# DiPho_PoE_adapter.net
KiCad netlist of a schematic drawn in Altium Designer
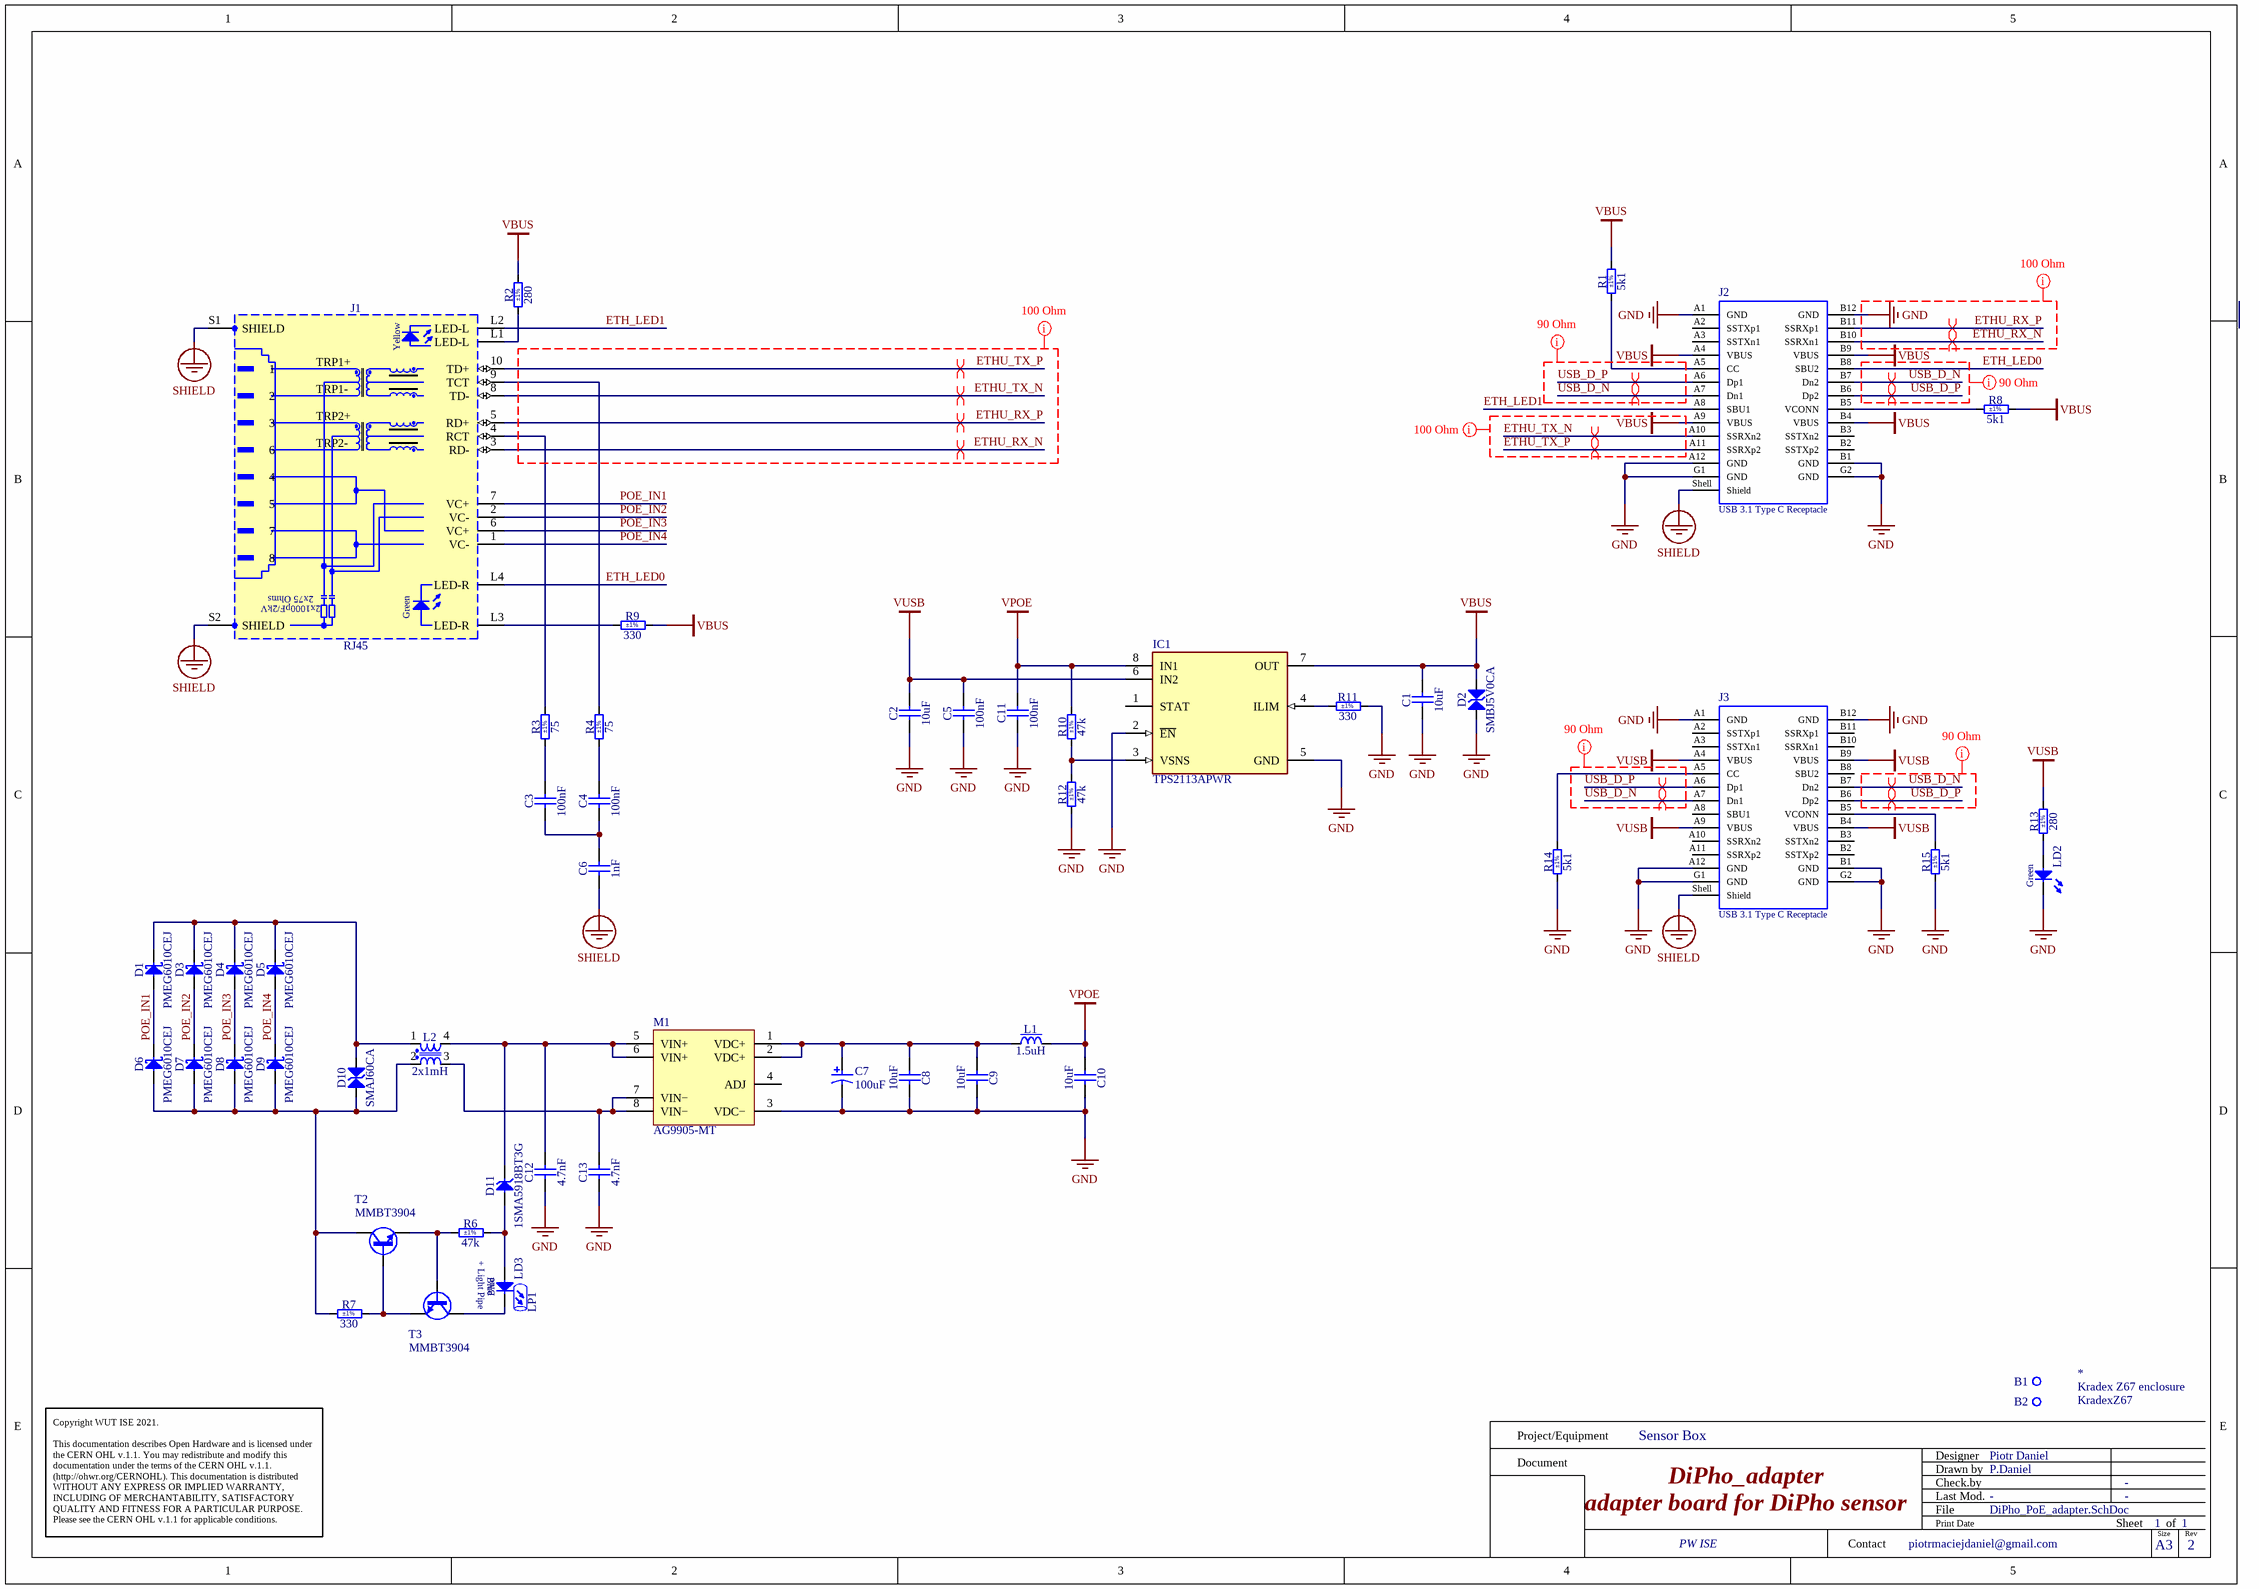
[diagram p0: DiPho_PoE_adapter.SchDoc]

(export (version "E")
  (design (tool "Eeschema 10.0.6"))
  (components
    (comp (ref "*") (value "KradexZ67") (footprint "KradexZ67") (libsource (lib "DiPho") (part "KradexZ67")))
    (comp (ref "B1")
      (value "Plated Hole")
      (footprint "MTG300_600")
      (description "Single Terminal Socket")
      (fields (field (name "PART NUMBER") "PLATED_HOLE3.0_PAD6.0") (field (name "AUTHOR") "CERN DEM JLC"))
      (libsource (lib "Eletro-mechanical") (part "Single Terminal Socket"))
    )
    (comp (ref "B2")
      (value "Plated Hole")
      (footprint "MTG300_600")
      (description "Single Terminal Socket")
      (fields (field (name "PART NUMBER") "PLATED_HOLE3.0_PAD6.0") (field (name "AUTHOR") "CERN DEM JLC"))
      (libsource (lib "Eletro-mechanical") (part "Single Terminal Socket"))
    )
    (comp (ref "C1")
      (value "10uF")
      (footprint "CAPC3225X270N")
      (description "Non-polarised capacitor")
      (fields
        (field (name "PART NUMBER") "CC1210_10UF_25V_10%_X7R")
        (field (name "VOLTAGE") "25V")
        (field (name "AUTHOR") "CERN DEM JLC")
      )
      (libsource (lib "Capacitors") (part "Capacitor - non polarized"))
    )
    (comp (ref "C2")
      (value "10uF")
      (footprint "CAPC3225X270N")
      (description "Non-polarised capacitor")
      (fields
        (field (name "PART NUMBER") "CC1210_10UF_25V_10%_X7R")
        (field (name "VOLTAGE") "25V")
        (field (name "AUTHOR") "CERN DEM JLC")
      )
      (libsource (lib "Capacitors") (part "Capacitor - non polarized"))
    )
    (comp (ref "C3")
      (value "100nF")
      (footprint "CAPC1608X90N")
      (description "Non-polarised capacitor")
      (fields
        (field (name "PART NUMBER") "CC0603_100NF_100V_10%_X7R")
        (field (name "VOLTAGE") "100V")
        (field (name "AUTHOR") "CERN DEM JLC")
      )
      (libsource (lib "Capacitors") (part "Capacitor - non polarized"))
    )
    (comp (ref "C4")
      (value "100nF")
      (footprint "CAPC1608X90N")
      (description "Non-polarised capacitor")
      (fields
        (field (name "PART NUMBER") "CC0603_100NF_100V_10%_X7R")
        (field (name "VOLTAGE") "100V")
        (field (name "AUTHOR") "CERN DEM JLC")
      )
      (libsource (lib "Capacitors") (part "Capacitor - non polarized"))
    )
    (comp (ref "C5")
      (value "100nF")
      (footprint "CAPC1608X90N")
      (description "Non-polarised capacitor")
      (fields
        (field (name "PART NUMBER") "CC0603_100NF_100V_10%_X7R")
        (field (name "VOLTAGE") "100V")
        (field (name "AUTHOR") "CERN DEM JLC")
      )
      (libsource (lib "Capacitors") (part "Capacitor - non polarized"))
    )
    (comp (ref "C6")
      (value "1nF")
      (footprint "CAPC3216X180N")
      (description "Non-polarised capacitor")
      (fields
        (field (name "PART NUMBER") "CC1206_1NF_2KV_10%_X7R")
        (field (name "VOLTAGE") "2kV")
        (field (name "AUTHOR") "CERN DEM JLC")
      )
      (libsource (lib "Capacitors") (part "Capacitor - non polarized"))
    )
    (comp (ref "C7")
      (value "100uF")
      (footprint "PNSC-EEEFK1C101P_L")
      (fields (field (name "MANUFACTURER") "Panasonic"))
      (libsource (lib "Altium Content Vault") (part "CAP-P-2"))
    )
    (comp (ref "C8")
      (value "10uF")
      (footprint "CAPC3225X270N")
      (description "Non-polarised capacitor")
      (fields
        (field (name "PART NUMBER") "CC1210_10UF_25V_10%_X7R")
        (field (name "VOLTAGE") "25V")
        (field (name "AUTHOR") "CERN DEM JLC")
      )
      (libsource (lib "Capacitors") (part "Capacitor - non polarized"))
    )
    (comp (ref "C9")
      (value "10uF")
      (footprint "CAPC3225X270N")
      (description "Non-polarised capacitor")
      (fields
        (field (name "PART NUMBER") "CC1210_10UF_25V_10%_X7R")
        (field (name "VOLTAGE") "25V")
        (field (name "AUTHOR") "CERN DEM JLC")
      )
      (libsource (lib "Capacitors") (part "Capacitor - non polarized"))
    )
    (comp (ref "C10")
      (value "10uF")
      (footprint "CAPC3225X270N")
      (description "Non-polarised capacitor")
      (fields
        (field (name "PART NUMBER") "CC1210_10UF_25V_10%_X7R")
        (field (name "VOLTAGE") "25V")
        (field (name "AUTHOR") "CERN DEM JLC")
      )
      (libsource (lib "Capacitors") (part "Capacitor - non polarized"))
    )
    (comp (ref "C11")
      (value "100nF")
      (footprint "CAPC1608X90N")
      (description "Non-polarised capacitor")
      (fields
        (field (name "PART NUMBER") "CC0603_100NF_100V_10%_X7R")
        (field (name "VOLTAGE") "100V")
        (field (name "AUTHOR") "CERN DEM JLC")
      )
      (libsource (lib "Capacitors") (part "Capacitor - non polarized"))
    )
    (comp (ref "C12")
      (value "4.7nF")
      (footprint "CAPC3216X180N")
      (description "Non-polarised capacitor")
      (fields
        (field (name "PART NUMBER") "CC1206_1NF_2KV_10%_X7R")
        (field (name "VOLTAGE") "2kV")
        (field (name "AUTHOR") "CERN DEM JLC")
      )
      (libsource (lib "Capacitors") (part "Capacitor - non polarized"))
    )
    (comp (ref "C13")
      (value "4.7nF")
      (footprint "CAPC3216X180N")
      (description "Non-polarised capacitor")
      (fields
        (field (name "PART NUMBER") "CC1206_1NF_2KV_10%_X7R")
        (field (name "VOLTAGE") "2kV")
        (field (name "AUTHOR") "CERN DEM JLC")
      )
      (libsource (lib "Capacitors") (part "Capacitor - non polarized"))
    )
    (comp (ref "D1")
      (value "PMEG6010CEJ")
      (footprint "SODFL2513X80N")
      (description "Schottky Diode")
      (fields
        (field (name "VOLTAGE") "60V")
        (field (name "POWER") "1A")
        (field (name "AUTHOR") "CERN DEM BC")
      )
      (libsource (lib "ICs And Semiconductors") (part "Diode Schottky"))
    )
    (comp (ref "D2")
      (value "SMBJ5V0CA")
      (footprint "DIOM5336X265N")
      (description "Transient Voltage Suppressor Diode (Bi-Directional)")
      (fields
        (field (name "VOLTAGE") "5V")
        (field (name "POWER") "600W")
        (field (name "AUTHOR") "CERN DEM JLC")
      )
      (libsource (lib "ICs And Semiconductors") (part "Diode TVS Bi-Directional"))
    )
    (comp (ref "D3")
      (value "PMEG6010CEJ")
      (footprint "SODFL2513X80N")
      (description "Schottky Diode")
      (fields
        (field (name "VOLTAGE") "60V")
        (field (name "POWER") "1A")
        (field (name "AUTHOR") "CERN DEM BC")
      )
      (libsource (lib "ICs And Semiconductors") (part "Diode Schottky"))
    )
    (comp (ref "D4")
      (value "PMEG6010CEJ")
      (footprint "SODFL2513X80N")
      (description "Schottky Diode")
      (fields
        (field (name "VOLTAGE") "60V")
        (field (name "POWER") "1A")
        (field (name "AUTHOR") "CERN DEM BC")
      )
      (libsource (lib "ICs And Semiconductors") (part "Diode Schottky"))
    )
    (comp (ref "D5")
      (value "PMEG6010CEJ")
      (footprint "SODFL2513X80N")
      (description "Schottky Diode")
      (fields
        (field (name "VOLTAGE") "60V")
        (field (name "POWER") "1A")
        (field (name "AUTHOR") "CERN DEM BC")
      )
      (libsource (lib "ICs And Semiconductors") (part "Diode Schottky"))
    )
    (comp (ref "D6")
      (value "PMEG6010CEJ")
      (footprint "SODFL2513X80N")
      (description "Schottky Diode")
      (fields
        (field (name "VOLTAGE") "60V")
        (field (name "POWER") "1A")
        (field (name "AUTHOR") "CERN DEM BC")
      )
      (libsource (lib "ICs And Semiconductors") (part "Diode Schottky"))
    )
    (comp (ref "D7")
      (value "PMEG6010CEJ")
      (footprint "SODFL2513X80N")
      (description "Schottky Diode")
      (fields
        (field (name "VOLTAGE") "60V")
        (field (name "POWER") "1A")
        (field (name "AUTHOR") "CERN DEM BC")
      )
      (libsource (lib "ICs And Semiconductors") (part "Diode Schottky"))
    )
    (comp (ref "D8")
      (value "PMEG6010CEJ")
      (footprint "SODFL2513X80N")
      (description "Schottky Diode")
      (fields
        (field (name "VOLTAGE") "60V")
        (field (name "POWER") "1A")
        (field (name "AUTHOR") "CERN DEM BC")
      )
      (libsource (lib "ICs And Semiconductors") (part "Diode Schottky"))
    )
    (comp (ref "D9")
      (value "PMEG6010CEJ")
      (footprint "SODFL2513X80N")
      (description "Schottky Diode")
      (fields
        (field (name "VOLTAGE") "60V")
        (field (name "POWER") "1A")
        (field (name "AUTHOR") "CERN DEM BC")
      )
      (libsource (lib "ICs And Semiconductors") (part "Diode Schottky"))
    )
    (comp (ref "D10")
      (value "SMAJ60CA")
      (footprint "DIOM5226X262N")
      (description "Transient Voltage Suppressor Diode (Bi-Directional)")
      (fields
        (field (name "VOLTAGE") "60V")
        (field (name "POWER") "400W")
        (field (name "AUTHOR") "CERN DEM JLC")
      )
      (libsource (lib "ICs And Semiconductors") (part "Diode TVS Bi-Directional"))
    )
    (comp (ref "D11")
      (value "1SMA5918BT3G")
      (footprint "DIOM5226X220N")
      (description "Zener Diode")
      (fields
        (field (name "VOLTAGE") "5.1V")
        (field (name "POWER") "1.5W")
        (field (name "AUTHOR") "CERN DEM JLC")
      )
      (libsource (lib "ICs And Semiconductors") (part "Diode Zener"))
    )
    (comp (ref "IC1")
      (value "TPS2113APWR")
      (footprint "FP-PW0008A-MFG")
      (description "IC OR CTRLR SRC SELECT 8TSSOP")
      (libsource (lib "Altium Content Vault") (part "883c2ec5d874d1801bc805f681b0625"))
    )
    (comp (ref "J1")
      (value "RJ45")
      (footprint "ABRACON_ARJM11C7-114-BA-EW2")
      (description "MagJack 10/100BaseT, PoE+, 1X1, OG/Y, -40 to 85*C, Tab Up, RoHS")
      (fields
        (field (name "PART NUMBER") "ARJM11C7-114-BA-EW2")
        (field (name "MANUFACTURER") "Abracon")
        (field (name "AUTHOR") "GK")
      )
      (libsource (lib "DiPho") (part "CON_ETH_POE_ARJM11C7"))
    )
    (comp (ref "J2")
      (value "USB 3.1 Type C Receptacle")
      (footprint "632723300011")
      (description "USB 3.1 Type C, Receptacle, Horizontal, THR")
      (fields
        (field (name "MANUFACTURER") "Wurth Elektronik")
        (field (name "MANUFACTURER PART NUMBER") "632723300011")
      )
      (libsource (lib "WR-USB_USB 3.1") (part "632723300011"))
    )
    (comp (ref "J3")
      (value "USB 3.1 Type C Receptacle")
      (footprint "632723300011")
      (description "USB 3.1 Type C, Receptacle, Horizontal, THR")
      (fields
        (field (name "MANUFACTURER") "Wurth Elektronik")
        (field (name "MANUFACTURER PART NUMBER") "632723300011")
      )
      (libsource (lib "WR-USB_USB 3.1") (part "632723300011"))
    )
    (comp (ref "L1")
      (value "1.5uH")
      (footprint "IND_COILCRAFT_1812CS")
      (description "Inductor With Core")
      (fields
        (field (name "PART NUMBER") "IND_1.5UH_2%_COILCRAFT_1812CS")
        (field (name "POWER") "430mA")
        (field (name "AUTHOR") "CERN DEM JMW")
      )
      (libsource (lib "Inductors & Transformers") (part "Inductor With Magnetic core"))
    )
    (comp (ref "L2")
      (value "2x1mH")
      (footprint "IND_WURTH_WE-SL2")
      (description "Inductor Common Mode")
      (fields
        (field (name "PART NUMBER") "IND_1MH_50%_WURTH_WE-SL2-744222")
        (field (name "POWER") "800mA")
        (field (name "AUTHOR") "CERN DEM JLC")
      )
      (libsource (lib "Inductors & Transformers") (part "Inductor Common Mode 1Dot-4 2Dot-3"))
    )
    (comp (ref "LD2")
      (value "Green")
      (footprint "LED_KINGBRIGHT_KPT-2012ZGC")
      (description "LED Green 1C 2A")
      (fields
        (field (name "PART NUMBER") "LED_KINGBRIGHT_KPT-2012ZGC")
        (field (name "MANUFACTURER") "KINGBRIGHT")
        (field (name "AUTHOR") "CERN DEM BC")
      )
      (libsource (lib "ICs And Semiconductors") (part "LED Green 1C 2A"))
    )
    (comp (ref "LD3")
      (value "Blue")
      (footprint "LED_KINGBRIGHT_KPT-2012VBC-D")
      (description "LED Blue 1C 2A")
      (fields
        (field (name "PART NUMBER") "LED_KINGBRIGHT_KPT-2012VBC-D")
        (field (name "MANUFACTURER") "KINGBRIGHT")
        (field (name "AUTHOR") "CERN DEM BC")
      )
      (libsource (lib "ICs And Semiconductors") (part "LED Blue 1C 2A"))
    )
    (comp (ref "LP1")
      (value "~")
      (footprint "LEDLP_DIALIGHT_515-1049F")
      (description "LED Light Pipe x1 Type1")
      (fields
        (field (name "PART NUMBER") "LEDLP_DIALIGHT_515-1049F")
        (field (name "MANUFACTURER") "DIALIGHT")
        (field (name "AUTHOR") "CERN DEM JLC")
      )
      (libsource (lib "ICs And Semiconductors") (part "LED Light Pipe x1 Type1"))
    )
    (comp (ref "M1")
      (value "AG9905-MT")
      (footprint "SILVERTEL_AG9900")
      (description "Ultra Miniature PoE, 5V, w/Thermal Protection")
      (fields (field (name "MANUFACTURER") "Silvertel"))
      (libsource (lib "DiPho") (part "AG9905-MT"))
    )
    (comp (ref "R1")
      (value "5k1")
      (footprint "RESC1608X55N")
      (description "Resistor - 1%")
      (fields
        (field (name "TOLERANCE") "±1%")
        (field (name "PART NUMBER") "R0603_5K1_1%_0.1W_100PPM")
        (field (name "POWER") "0.1W")
        (field (name "AUTHOR") "CERN DEM JLC")
      )
      (libsource (lib "Resistors") (part "Resistor - 1%"))
    )
    (comp (ref "R2")
      (value "280")
      (footprint "RESC1608X55N")
      (description "Resistor - 1%")
      (fields
        (field (name "TOLERANCE") "±1%")
        (field (name "PART NUMBER") "R0603_280R_1%_0.1W_100PPM")
        (field (name "POWER") "0.1W")
        (field (name "AUTHOR") "CERN DEM JLC")
      )
      (libsource (lib "Resistors") (part "Resistor - 1%"))
    )
    (comp (ref "R3")
      (value "75")
      (footprint "RESC1608X55N")
      (description "Resistor - 1%")
      (fields
        (field (name "TOLERANCE") "±1%")
        (field (name "PART NUMBER") "R0603_75R_1%_0.1W_100PPM")
        (field (name "POWER") "0.1W")
        (field (name "AUTHOR") "CERN DEM JLC")
      )
      (libsource (lib "Resistors") (part "Resistor - 1%"))
    )
    (comp (ref "R4")
      (value "75")
      (footprint "RESC1608X55N")
      (description "Resistor - 1%")
      (fields
        (field (name "TOLERANCE") "±1%")
        (field (name "PART NUMBER") "R0603_75R_1%_0.1W_100PPM")
        (field (name "POWER") "0.1W")
        (field (name "AUTHOR") "CERN DEM JLC")
      )
      (libsource (lib "Resistors") (part "Resistor - 1%"))
    )
    (comp (ref "R6")
      (value "47k")
      (footprint "RESC1608X55N")
      (description "Resistor - 1%")
      (fields
        (field (name "TOLERANCE") "±1%")
        (field (name "PART NUMBER") "R0603_47K_1%_0.1W_100PPM")
        (field (name "POWER") "0.1W")
        (field (name "AUTHOR") "CERN DEM JLC")
      )
      (libsource (lib "Resistors") (part "Resistor - 1%"))
    )
    (comp (ref "R7")
      (value "330")
      (footprint "RESC1608X55N")
      (description "Resistor - 1%")
      (fields
        (field (name "TOLERANCE") "±1%")
        (field (name "PART NUMBER") "R0603_330R_1%_0.1W_100PPM")
        (field (name "POWER") "0.1W")
        (field (name "AUTHOR") "CERN DEM JLC")
      )
      (libsource (lib "Resistors") (part "Resistor - 1%"))
    )
    (comp (ref "R8")
      (value "5k1")
      (footprint "RESC1608X55N")
      (description "Resistor - 1%")
      (fields
        (field (name "TOLERANCE") "±1%")
        (field (name "PART NUMBER") "R0603_5K1_1%_0.1W_100PPM")
        (field (name "POWER") "0.1W")
        (field (name "AUTHOR") "CERN DEM JLC")
      )
      (libsource (lib "Resistors") (part "Resistor - 1%"))
    )
    (comp (ref "R9")
      (value "330")
      (footprint "RESC1608X55N")
      (description "Resistor - 1%")
      (fields
        (field (name "TOLERANCE") "±1%")
        (field (name "PART NUMBER") "R0603_330R_1%_0.1W_100PPM")
        (field (name "POWER") "0.1W")
        (field (name "AUTHOR") "CERN DEM JLC")
      )
      (libsource (lib "Resistors") (part "Resistor - 1%"))
    )
    (comp (ref "R10")
      (value "47k")
      (footprint "RESC1608X55N")
      (description "Resistor - 1%")
      (fields
        (field (name "TOLERANCE") "±1%")
        (field (name "PART NUMBER") "R0603_47K_1%_0.1W_100PPM")
        (field (name "POWER") "0.1W")
        (field (name "AUTHOR") "CERN DEM JLC")
      )
      (libsource (lib "Resistors") (part "Resistor - 1%"))
    )
    (comp (ref "R11")
      (value "330")
      (footprint "RESC1608X55N")
      (description "Resistor - 1%")
      (fields
        (field (name "TOLERANCE") "±1%")
        (field (name "PART NUMBER") "R0603_330R_1%_0.1W_100PPM")
        (field (name "POWER") "0.1W")
        (field (name "AUTHOR") "CERN DEM JLC")
      )
      (libsource (lib "Resistors") (part "Resistor - 1%"))
    )
    (comp (ref "R12")
      (value "47k")
      (footprint "RESC1608X55N")
      (description "Resistor - 1%")
      (fields
        (field (name "TOLERANCE") "±1%")
        (field (name "PART NUMBER") "R0603_47K_1%_0.1W_100PPM")
        (field (name "POWER") "0.1W")
        (field (name "AUTHOR") "CERN DEM JLC")
      )
      (libsource (lib "Resistors") (part "Resistor - 1%"))
    )
    (comp (ref "R13")
      (value "280")
      (footprint "RESC1608X55N")
      (description "Resistor - 1%")
      (fields
        (field (name "TOLERANCE") "±1%")
        (field (name "PART NUMBER") "R0603_280R_1%_0.1W_100PPM")
        (field (name "POWER") "0.1W")
        (field (name "AUTHOR") "CERN DEM JLC")
      )
      (libsource (lib "Resistors") (part "Resistor - 1%"))
    )
    (comp (ref "R14")
      (value "5k1")
      (footprint "RESC1608X55N")
      (description "Resistor - 1%")
      (fields
        (field (name "TOLERANCE") "±1%")
        (field (name "PART NUMBER") "R0603_5K1_1%_0.1W_100PPM")
        (field (name "POWER") "0.1W")
        (field (name "AUTHOR") "CERN DEM JLC")
      )
      (libsource (lib "Resistors") (part "Resistor - 1%"))
    )
    (comp (ref "R15")
      (value "5k1")
      (footprint "RESC1608X55N")
      (description "Resistor - 1%")
      (fields
        (field (name "TOLERANCE") "±1%")
        (field (name "PART NUMBER") "R0603_5K1_1%_0.1W_100PPM")
        (field (name "POWER") "0.1W")
        (field (name "AUTHOR") "CERN DEM JLC")
      )
      (libsource (lib "Resistors") (part "Resistor - 1%"))
    )
    (comp (ref "T2")
      (value "MMBT3904")
      (footprint "SOT95P230X110-3N")
      (description "NPN Transistor")
      (fields (field (name "MANUFACTURER") "NXP SEMICONDUCTORS") (field (name "AUTHOR") "CERN DEM JLC"))
      (libsource (lib "ICs And Semiconductors") (part "NPN B1 E2 C3"))
    )
    (comp (ref "T3")
      (value "MMBT3904")
      (footprint "SOT95P230X110-3N")
      (description "NPN Transistor")
      (fields (field (name "MANUFACTURER") "NXP SEMICONDUCTORS") (field (name "AUTHOR") "CERN DEM JLC"))
      (libsource (lib "ICs And Semiconductors") (part "NPN B1 E2 C3"))
    )
  )
  (nets
    (net (code "1") (name "/ETHU_RX_N") (class "Default")
      (node (ref "J1") (pin "3") (pinfunction "RD-_3") (pintype "bidirectional"))
      (node (ref "J2") (pin "B10") (pinfunction "SSRXn1_B10") (pintype "passive"))
    )
    (net (code "2") (name "/ETHU_RX_P") (class "Default")
      (node (ref "J1") (pin "5") (pinfunction "RD+_5") (pintype "bidirectional"))
      (node (ref "J2") (pin "B11") (pinfunction "SSRXp1_B11") (pintype "passive"))
    )
    (net (code "3") (name "/ETHU_TX_N") (class "Default")
      (node (ref "J1") (pin "8") (pinfunction "TD-_8") (pintype "bidirectional"))
      (node (ref "J2") (pin "A10") (pinfunction "SSRXn2_A10") (pintype "passive"))
    )
    (net (code "4") (name "/ETHU_TX_P") (class "Default")
      (node (ref "J1") (pin "10") (pinfunction "TD+_10") (pintype "bidirectional"))
      (node (ref "J2") (pin "A11") (pinfunction "SSRXp2_A11") (pintype "passive"))
    )
    (net (code "5") (name "/ETH_LED0") (class "Default")
      (node (ref "J1") (pin "L4") (pinfunction "LED-R_L4") (pintype "passive"))
      (node (ref "J2") (pin "B8") (pinfunction "SBU2_B8") (pintype "passive"))
    )
    (net (code "6") (name "/ETH_LED1") (class "Default")
      (node (ref "J1") (pin "L2") (pinfunction "LED-L_L2") (pintype "passive"))
      (node (ref "J2") (pin "A8") (pinfunction "SBU1_A8") (pintype "passive"))
    )
    (net (code "7") (name "/POE_IN1") (class "Default")
      (node (ref "D1") (pin "2") (pinfunction "A_2") (pintype "passive"))
      (node (ref "D6") (pin "1") (pinfunction "C_1") (pintype "passive"))
      (node (ref "J1") (pin "7") (pinfunction "VC+_7") (pintype "passive"))
    )
    (net (code "8") (name "/POE_IN2") (class "Default")
      (node (ref "D3") (pin "2") (pinfunction "A_2") (pintype "passive"))
      (node (ref "D7") (pin "1") (pinfunction "C_1") (pintype "passive"))
      (node (ref "J1") (pin "2") (pinfunction "VC-_2") (pintype "passive"))
    )
    (net (code "9") (name "/POE_IN3") (class "Default")
      (node (ref "D4") (pin "2") (pinfunction "A_2") (pintype "passive"))
      (node (ref "D8") (pin "1") (pinfunction "C_1") (pintype "passive"))
      (node (ref "J1") (pin "6") (pinfunction "VC+_6") (pintype "passive"))
    )
    (net (code "10") (name "/POE_IN4") (class "Default")
      (node (ref "D5") (pin "2") (pinfunction "A_2") (pintype "passive"))
      (node (ref "D9") (pin "1") (pinfunction "C_1") (pintype "passive"))
      (node (ref "J1") (pin "1") (pinfunction "VC-_1") (pintype "passive"))
    )
    (net (code "11") (name "/USB_D_N") (class "Default")
      (node (ref "J2") (pin "A7") (pinfunction "Dn1_A7") (pintype "passive"))
      (node (ref "J2") (pin "B7") (pinfunction "Dn2_B7") (pintype "passive"))
      (node (ref "J3") (pin "A7") (pinfunction "Dn1_A7") (pintype "passive"))
      (node (ref "J3") (pin "B7") (pinfunction "Dn2_B7") (pintype "passive"))
    )
    (net (code "12") (name "/USB_D_P") (class "Default")
      (node (ref "J2") (pin "A6") (pinfunction "Dp1_A6") (pintype "passive"))
      (node (ref "J2") (pin "B6") (pinfunction "Dp2_B6") (pintype "passive"))
      (node (ref "J3") (pin "A6") (pinfunction "Dp1_A6") (pintype "passive"))
      (node (ref "J3") (pin "B6") (pinfunction "Dp2_B6") (pintype "passive"))
    )
    (net (code "13") (name "GND") (class "Default")
      (node (ref "C1") (pin "1") (pinfunction "1_1") (pintype "passive"))
      (node (ref "C10") (pin "2") (pinfunction "2_2") (pintype "passive"))
      (node (ref "C11") (pin "1") (pinfunction "1_1") (pintype "passive"))
      (node (ref "C12") (pin "1") (pinfunction "1_1") (pintype "passive"))
      (node (ref "C13") (pin "1") (pinfunction "1_1") (pintype "passive"))
      (node (ref "C2") (pin "1") (pinfunction "1_1") (pintype "passive"))
      (node (ref "C5") (pin "1") (pinfunction "1_1") (pintype "passive"))
      (node (ref "C7") (pin "2") (pinfunction "2_2") (pintype "passive"))
      (node (ref "C8") (pin "2") (pinfunction "2_2") (pintype "passive"))
      (node (ref "C9") (pin "2") (pinfunction "2_2") (pintype "passive"))
      (node (ref "D2") (pin "1") (pinfunction "1_1") (pintype "passive"))
      (node (ref "IC1") (pin "2") (pinfunction "~{EN}_2") (pintype "input"))
      (node (ref "IC1") (pin "5") (pinfunction "GND_5") (pintype "power_in"))
      (node (ref "J2") (pin "A1") (pinfunction "GND_A1") (pintype "passive"))
      (node (ref "J2") (pin "A12") (pinfunction "GND_A12") (pintype "passive"))
      (node (ref "J2") (pin "B1") (pinfunction "GND_B1") (pintype "passive"))
      (node (ref "J2") (pin "B12") (pinfunction "GND_B12") (pintype "passive"))
      (node (ref "J2") (pin "G1") (pinfunction "GND_G1") (pintype "passive"))
      (node (ref "J2") (pin "G2") (pinfunction "GND_G2") (pintype "passive"))
      (node (ref "J3") (pin "A1") (pinfunction "GND_A1") (pintype "passive"))
      (node (ref "J3") (pin "A12") (pinfunction "GND_A12") (pintype "passive"))
      (node (ref "J3") (pin "B1") (pinfunction "GND_B1") (pintype "passive"))
      (node (ref "J3") (pin "B12") (pinfunction "GND_B12") (pintype "passive"))
      (node (ref "J3") (pin "G1") (pinfunction "GND_G1") (pintype "passive"))
      (node (ref "J3") (pin "G2") (pinfunction "GND_G2") (pintype "passive"))
      (node (ref "LD2") (pin "1") (pinfunction "C_1") (pintype "passive"))
      (node (ref "M1") (pin "3") (pinfunction "VDC−_3") (pintype "passive"))
      (node (ref "R11") (pin "2") (pinfunction "2_2") (pintype "passive"))
      (node (ref "R12") (pin "1") (pinfunction "1_1") (pintype "passive"))
      (node (ref "R14") (pin "1") (pinfunction "1_1") (pintype "passive"))
      (node (ref "R15") (pin "1") (pinfunction "1_1") (pintype "passive"))
    )
    (net (code "14") (name "Net-(C3-Pad1)") (class "Default")
      (node (ref "C3") (pin "1") (pinfunction "1_1") (pintype "passive"))
      (node (ref "C4") (pin "1") (pinfunction "1_1") (pintype "passive"))
      (node (ref "C6") (pin "2") (pinfunction "2_2") (pintype "passive"))
    )
    (net (code "15") (name "Net-(C3-Pad2)") (class "Default")
      (node (ref "C3") (pin "2") (pinfunction "2_2") (pintype "passive"))
      (node (ref "R3") (pin "1") (pinfunction "1_1") (pintype "passive"))
    )
    (net (code "16") (name "Net-(C4-Pad2)") (class "Default")
      (node (ref "C4") (pin "2") (pinfunction "2_2") (pintype "passive"))
      (node (ref "R4") (pin "1") (pinfunction "1_1") (pintype "passive"))
    )
    (net (code "17") (name "Net-(C7-Pad1)") (class "Default")
      (node (ref "C7") (pin "1") (pinfunction "1_1") (pintype "passive"))
      (node (ref "C8") (pin "1") (pinfunction "1_1") (pintype "passive"))
      (node (ref "C9") (pin "1") (pinfunction "1_1") (pintype "passive"))
      (node (ref "L1") (pin "1") (pinfunction "1_1") (pintype "passive"))
      (node (ref "M1") (pin "1") (pinfunction "VDC+_1") (pintype "passive"))
      (node (ref "M1") (pin "2") (pinfunction "VDC+_2") (pintype "passive"))
    )
    (net (code "18") (name "Net-(C13-Pad2)") (class "Default")
      (node (ref "C13") (pin "2") (pinfunction "2_2") (pintype "passive"))
      (node (ref "L2") (pin "3") (pinfunction "3_3") (pintype "passive"))
      (node (ref "M1") (pin "7") (pinfunction "VIN−_7") (pintype "passive"))
      (node (ref "M1") (pin "8") (pinfunction "VIN−_8") (pintype "passive"))
    )
    (net (code "19") (name "Net-(D1-C)") (class "Default")
      (node (ref "D1") (pin "1") (pinfunction "C_1") (pintype "passive"))
      (node (ref "D10") (pin "2") (pinfunction "2_2") (pintype "passive"))
      (node (ref "D3") (pin "1") (pinfunction "C_1") (pintype "passive"))
      (node (ref "D4") (pin "1") (pinfunction "C_1") (pintype "passive"))
      (node (ref "D5") (pin "1") (pinfunction "C_1") (pintype "passive"))
      (node (ref "L2") (pin "1") (pinfunction "1_1") (pintype "passive"))
    )
    (net (code "20") (name "Net-(D6-A)") (class "Default")
      (node (ref "D10") (pin "1") (pinfunction "1_1") (pintype "passive"))
      (node (ref "D6") (pin "2") (pinfunction "A_2") (pintype "passive"))
      (node (ref "D7") (pin "2") (pinfunction "A_2") (pintype "passive"))
      (node (ref "D8") (pin "2") (pinfunction "A_2") (pintype "passive"))
      (node (ref "D9") (pin "2") (pinfunction "A_2") (pintype "passive"))
      (node (ref "L2") (pin "2") (pinfunction "2_2") (pintype "passive"))
      (node (ref "R7") (pin "1") (pinfunction "1_1") (pintype "passive"))
      (node (ref "T2") (pin "3") (pinfunction "C_3") (pintype "passive"))
    )
    (net (code "21") (name "Net-(D11-A)") (class "Default")
      (node (ref "D11") (pin "2") (pinfunction "A_2") (pintype "passive"))
      (node (ref "LD3") (pin "2") (pinfunction "A_2") (pintype "passive"))
      (node (ref "R6") (pin "2") (pinfunction "2_2") (pintype "passive"))
    )
    (net (code "22") (name "Net-(D11-C)") (class "Default")
      (node (ref "C12") (pin "2") (pinfunction "2_2") (pintype "passive"))
      (node (ref "D11") (pin "1") (pinfunction "C_1") (pintype "passive"))
      (node (ref "L2") (pin "4") (pinfunction "4_4") (pintype "passive"))
      (node (ref "M1") (pin "5") (pinfunction "VIN+_5") (pintype "passive"))
      (node (ref "M1") (pin "6") (pinfunction "VIN+_6") (pintype "passive"))
    )
    (net (code "23") (name "Net-(IC1-ILIM)") (class "Default")
      (node (ref "IC1") (pin "4") (pinfunction "ILIM_4") (pintype "input"))
      (node (ref "R11") (pin "1") (pinfunction "1_1") (pintype "passive"))
    )
    (net (code "24") (name "Net-(IC1-VSNS)") (class "Default")
      (node (ref "IC1") (pin "3") (pinfunction "VSNS_3") (pintype "input"))
      (node (ref "R10") (pin "1") (pinfunction "1_1") (pintype "passive"))
      (node (ref "R12") (pin "2") (pinfunction "2_2") (pintype "passive"))
    )
    (net (code "25") (name "Net-(J1-LED-L-PadL1)") (class "Default")
      (node (ref "J1") (pin "L1") (pinfunction "LED-L_L1") (pintype "passive"))
      (node (ref "R2") (pin "1") (pinfunction "1_1") (pintype "passive"))
    )
    (net (code "26") (name "Net-(J1-LED-R-PadL3)") (class "Default")
      (node (ref "J1") (pin "L3") (pinfunction "LED-R_L3") (pintype "passive"))
      (node (ref "R9") (pin "1") (pinfunction "1_1") (pintype "passive"))
    )
    (net (code "27") (name "Net-(J1-RCT)") (class "Default")
      (node (ref "J1") (pin "4") (pinfunction "RCT_4") (pintype "bidirectional"))
      (node (ref "R3") (pin "2") (pinfunction "2_2") (pintype "passive"))
    )
    (net (code "28") (name "Net-(J1-TCT)") (class "Default")
      (node (ref "J1") (pin "9") (pinfunction "TCT_9") (pintype "bidirectional"))
      (node (ref "R4") (pin "2") (pinfunction "2_2") (pintype "passive"))
    )
    (net (code "29") (name "Net-(J2-CC)") (class "Default")
      (node (ref "J2") (pin "A5") (pinfunction "CC_A5") (pintype "passive"))
      (node (ref "R1") (pin "1") (pinfunction "1_1") (pintype "passive"))
    )
    (net (code "30") (name "Net-(J2-VCONN)") (class "Default")
      (node (ref "J2") (pin "B5") (pinfunction "VCONN_B5") (pintype "passive"))
      (node (ref "R8") (pin "1") (pinfunction "1_1") (pintype "passive"))
    )
    (net (code "31") (name "Net-(J3-CC)") (class "Default")
      (node (ref "J3") (pin "A5") (pinfunction "CC_A5") (pintype "passive"))
      (node (ref "R14") (pin "2") (pinfunction "2_2") (pintype "passive"))
    )
    (net (code "32") (name "Net-(J3-VCONN)") (class "Default")
      (node (ref "J3") (pin "B5") (pinfunction "VCONN_B5") (pintype "passive"))
      (node (ref "R15") (pin "2") (pinfunction "2_2") (pintype "passive"))
    )
    (net (code "33") (name "Net-(LD2-A)") (class "Default")
      (node (ref "LD2") (pin "2") (pinfunction "A_2") (pintype "passive"))
      (node (ref "R13") (pin "1") (pinfunction "1_1") (pintype "passive"))
    )
    (net (code "34") (name "Net-(LD3-C)") (class "Default")
      (node (ref "LD3") (pin "1") (pinfunction "C_1") (pintype "passive"))
      (node (ref "T3") (pin "3") (pinfunction "C_3") (pintype "passive"))
    )
    (net (code "35") (name "Net-(T2-B)") (class "Default")
      (node (ref "R7") (pin "2") (pinfunction "2_2") (pintype "passive"))
      (node (ref "T2") (pin "1") (pinfunction "B_1") (pintype "passive"))
      (node (ref "T3") (pin "2") (pinfunction "E_2") (pintype "passive"))
    )
    (net (code "36") (name "Net-(T2-E)") (class "Default")
      (node (ref "R6") (pin "1") (pinfunction "1_1") (pintype "passive"))
      (node (ref "T2") (pin "2") (pinfunction "E_2") (pintype "passive"))
      (node (ref "T3") (pin "1") (pinfunction "B_1") (pintype "passive"))
    )
    (net (code "37") (name "SHIELD") (class "Default")
      (node (ref "C6") (pin "1") (pinfunction "1_1") (pintype "passive"))
      (node (ref "J1") (pin "S1") (pinfunction "SHIELD_S1") (pintype "power_in"))
      (node (ref "J1") (pin "S2") (pinfunction "SHIELD_S2") (pintype "power_in"))
      (node (ref "J2") (pin "Shell") (pinfunction "Shield_Shell") (pintype "passive"))
      (node (ref "J3") (pin "Shell") (pinfunction "Shield_Shell") (pintype "passive"))
    )
    (net (code "38") (name "VBUS") (class "Default")
      (node (ref "C1") (pin "2") (pinfunction "2_2") (pintype "passive"))
      (node (ref "D2") (pin "2") (pinfunction "2_2") (pintype "passive"))
      (node (ref "IC1") (pin "7") (pinfunction "OUT_7") (pintype "power_in"))
      (node (ref "J2") (pin "A4") (pinfunction "VBUS_A4") (pintype "passive"))
      (node (ref "J2") (pin "A9") (pinfunction "VBUS_A9") (pintype "passive"))
      (node (ref "J2") (pin "B4") (pinfunction "VBUS_B4") (pintype "passive"))
      (node (ref "J2") (pin "B9") (pinfunction "VBUS_B9") (pintype "passive"))
      (node (ref "R1") (pin "2") (pinfunction "2_2") (pintype "passive"))
      (node (ref "R2") (pin "2") (pinfunction "2_2") (pintype "passive"))
      (node (ref "R8") (pin "2") (pinfunction "2_2") (pintype "passive"))
      (node (ref "R9") (pin "2") (pinfunction "2_2") (pintype "passive"))
    )
    (net (code "39") (name "VPOE") (class "Default")
      (node (ref "C10") (pin "1") (pinfunction "1_1") (pintype "passive"))
      (node (ref "C11") (pin "2") (pinfunction "2_2") (pintype "passive"))
      (node (ref "IC1") (pin "8") (pinfunction "IN1_8") (pintype "power_in"))
      (node (ref "L1") (pin "2") (pinfunction "2_2") (pintype "passive"))
      (node (ref "R10") (pin "2") (pinfunction "2_2") (pintype "passive"))
    )
    (net (code "40") (name "VUSB") (class "Default")
      (node (ref "C2") (pin "2") (pinfunction "2_2") (pintype "passive"))
      (node (ref "C5") (pin "2") (pinfunction "2_2") (pintype "passive"))
      (node (ref "IC1") (pin "6") (pinfunction "IN2_6") (pintype "power_in"))
      (node (ref "J3") (pin "A4") (pinfunction "VBUS_A4") (pintype "passive"))
      (node (ref "J3") (pin "A9") (pinfunction "VBUS_A9") (pintype "passive"))
      (node (ref "J3") (pin "B4") (pinfunction "VBUS_B4") (pintype "passive"))
      (node (ref "J3") (pin "B9") (pinfunction "VBUS_B9") (pintype "passive"))
      (node (ref "R13") (pin "2") (pinfunction "2_2") (pintype "passive"))
    )
    (net (code "41") (name "unconnected-(B1-Pad1)") (class "Default")
      (node (ref "B1") (pin "1") (pinfunction "1_1") (pintype "bidirectional"))
    )
    (net (code "42") (name "unconnected-(B2-Pad1)") (class "Default")
      (node (ref "B2") (pin "1") (pinfunction "1_1") (pintype "bidirectional"))
    )
    (net (code "43") (name "unconnected-(IC1-STAT-Pad1)") (class "Default")
      (node (ref "IC1") (pin "1") (pinfunction "STAT_1") (pintype "tri_state"))
    )
    (net (code "44") (name "unconnected-(J2-SSTXn1-PadA3)") (class "Default")
      (node (ref "J2") (pin "A3") (pinfunction "SSTXn1_A3") (pintype "passive"))
    )
    (net (code "45") (name "unconnected-(J2-SSTXn2-PadB3)") (class "Default")
      (node (ref "J2") (pin "B3") (pinfunction "SSTXn2_B3") (pintype "passive"))
    )
    (net (code "46") (name "unconnected-(J2-SSTXp1-PadA2)") (class "Default")
      (node (ref "J2") (pin "A2") (pinfunction "SSTXp1_A2") (pintype "passive"))
    )
    (net (code "47") (name "unconnected-(J2-SSTXp2-PadB2)") (class "Default")
      (node (ref "J2") (pin "B2") (pinfunction "SSTXp2_B2") (pintype "passive"))
    )
    (net (code "48") (name "unconnected-(J3-SBU1-PadA8)") (class "Default")
      (node (ref "J3") (pin "A8") (pinfunction "SBU1_A8") (pintype "passive"))
    )
    (net (code "49") (name "unconnected-(J3-SBU2-PadB8)") (class "Default")
      (node (ref "J3") (pin "B8") (pinfunction "SBU2_B8") (pintype "passive"))
    )
    (net (code "50") (name "unconnected-(J3-SSRXn1-PadB10)") (class "Default")
      (node (ref "J3") (pin "B10") (pinfunction "SSRXn1_B10") (pintype "passive"))
    )
    (net (code "51") (name "unconnected-(J3-SSRXn2-PadA10)") (class "Default")
      (node (ref "J3") (pin "A10") (pinfunction "SSRXn2_A10") (pintype "passive"))
    )
    (net (code "52") (name "unconnected-(J3-SSRXp1-PadB11)") (class "Default")
      (node (ref "J3") (pin "B11") (pinfunction "SSRXp1_B11") (pintype "passive"))
    )
    (net (code "53") (name "unconnected-(J3-SSRXp2-PadA11)") (class "Default")
      (node (ref "J3") (pin "A11") (pinfunction "SSRXp2_A11") (pintype "passive"))
    )
    (net (code "54") (name "unconnected-(J3-SSTXn1-PadA3)") (class "Default")
      (node (ref "J3") (pin "A3") (pinfunction "SSTXn1_A3") (pintype "passive"))
    )
    (net (code "55") (name "unconnected-(J3-SSTXn2-PadB3)") (class "Default")
      (node (ref "J3") (pin "B3") (pinfunction "SSTXn2_B3") (pintype "passive"))
    )
    (net (code "56") (name "unconnected-(J3-SSTXp1-PadA2)") (class "Default")
      (node (ref "J3") (pin "A2") (pinfunction "SSTXp1_A2") (pintype "passive"))
    )
    (net (code "57") (name "unconnected-(J3-SSTXp2-PadB2)") (class "Default")
      (node (ref "J3") (pin "B2") (pinfunction "SSTXp2_B2") (pintype "passive"))
    )
    (net (code "58") (name "unconnected-(M1-ADJ-Pad4)") (class "Default")
      (node (ref "M1") (pin "4") (pinfunction "ADJ_4") (pintype "passive"))
    )
  )
)
